# fl3xwatch.net
KiCad netlist of a schematic drawn in EAGLE
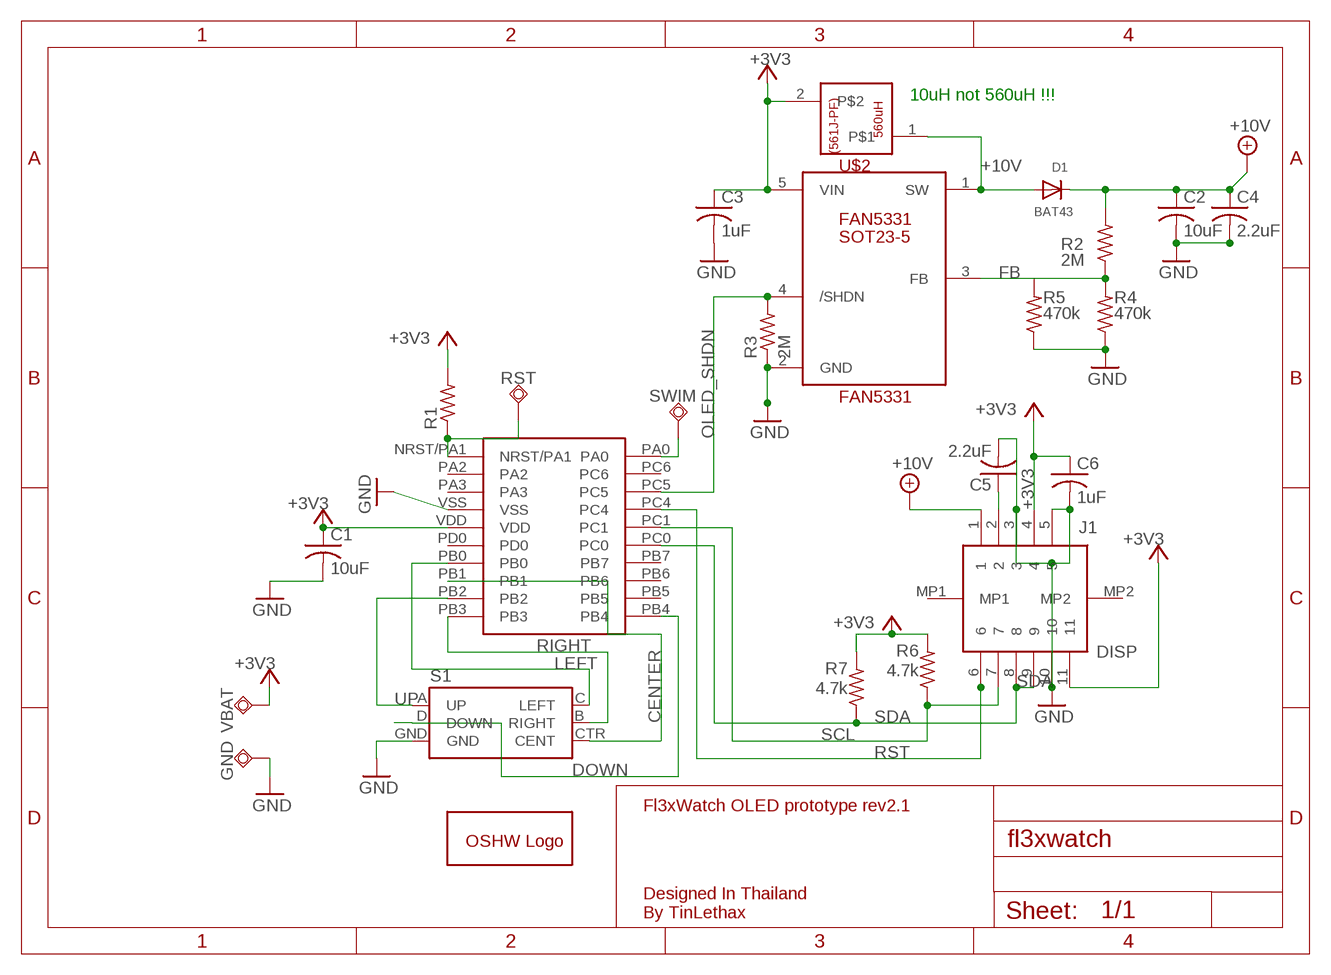
[diagram p0: schematic, sheet 1]

(export (version "E")
  (design (tool "Eeschema 10.0.6"))
  (components
    (comp (ref "C1")
      (value "10uF")
      (footprint "eagle-import:C0805")
      (libsource (lib "eagle-import") (part "C-USC0805"))
    )
    (comp (ref "C2")
      (value "10uF")
      (footprint "eagle-import:C0805")
      (libsource (lib "eagle-import") (part "C-USC0805"))
    )
    (comp (ref "C3")
      (value "1uF")
      (footprint "eagle-import:C0603")
      (libsource (lib "eagle-import") (part "C-USC0603"))
    )
    (comp (ref "C4")
      (value "2.2uF")
      (footprint "eagle-import:C0603")
      (libsource (lib "eagle-import") (part "C-USC0603"))
    )
    (comp (ref "C5")
      (value "2.2uF")
      (footprint "eagle-import:C0603")
      (libsource (lib "eagle-import") (part "C-USC0603"))
    )
    (comp (ref "C6")
      (value "1uF")
      (footprint "eagle-import:C0603")
      (libsource (lib "eagle-import") (part "C-USC0603"))
    )
    (comp (ref "D1")
      (value "BAT43")
      (footprint "eagle-import:SOD-323F")
      (libsource (lib "eagle-import") (part "DIODESOD-323F"))
    )
    (comp (ref "GND")
      (value "TPSQTP20SQ")
      (footprint "eagle-import:TP20SQ")
      (libsource (lib "eagle-import") (part "TPSQTP20SQ"))
    )
    (comp (ref "GOLD_ORB_SM1")
      (value "OSHWLOGOLOGO5MM")
      (footprint "eagle-import:OSHW_5MM")
      (libsource (lib "eagle-import") (part "OSHWLOGOLOGO5MM"))
    )
    (comp (ref "J1")
      (value "DISP")
      (footprint "eagle-import:FH35C11S03SHW50")
      (fields
        (field (name "MANUFACTURER_PART_NUMBER") "FH35C-11S-0.3SHW(50)")
        (field (name "MOUSER_PART_NUMBER") "798-FH35C11S03SHW50")
      )
      (libsource (lib "eagle-import") (part "FH35C-11S-0.3SHW_50_"))
    )
    (comp (ref "L1")
      (value "10uH")
      (footprint "eagle-import:INDC4526X50N")
      (libsource (lib "eagle-import") (part "NL453232T-561J-PF"))
    )
    (comp (ref "R1")
      (value "R-US_R0603")
      (footprint "eagle-import:R0603")
      (libsource (lib "eagle-import") (part "R-US_R0603"))
    )
    (comp (ref "R2")
      (value "2M")
      (footprint "eagle-import:R0603")
      (libsource (lib "eagle-import") (part "R-US_R0603"))
    )
    (comp (ref "R3")
      (value "2M")
      (footprint "eagle-import:R0603")
      (libsource (lib "eagle-import") (part "R-US_R0603"))
    )
    (comp (ref "R4")
      (value "470k")
      (footprint "eagle-import:R0805")
      (libsource (lib "eagle-import") (part "R-US_R0805"))
    )
    (comp (ref "R5")
      (value "470k")
      (footprint "eagle-import:R0805")
      (libsource (lib "eagle-import") (part "R-US_R0805"))
    )
    (comp (ref "R6")
      (value "4.7k")
      (footprint "eagle-import:R0603")
      (libsource (lib "eagle-import") (part "R-US_R0603"))
    )
    (comp (ref "R7")
      (value "4.7k")
      (footprint "eagle-import:R0603")
      (libsource (lib "eagle-import") (part "R-US_R0603"))
    )
    (comp (ref "RST")
      (value "TPSQTP15R")
      (footprint "eagle-import:TP15R")
      (libsource (lib "eagle-import") (part "TPSQTP15R"))
    )
    (comp (ref "S1")
      (value "SPARKFUN-ELECTROMECHANICAL_JOYSTICK_MINI")
      (footprint "eagle-import:SPARKFUN-ELECTROMECHANICAL_JOYSTICK_MINI")
      (libsource (lib "eagle-import") (part "SPARKFUN-ELECTROMECHANICAL_JOYSTICK_MINI"))
    )
    (comp (ref "SWIM")
      (value "TPSQTP15R")
      (footprint "eagle-import:TP15R")
      (libsource (lib "eagle-import") (part "TPSQTP15R"))
    )
    (comp (ref "U$1")
      (value "STM8L151F3")
      (footprint "eagle-import:UFQFPN-20")
      (libsource (lib "eagle-import") (part "STM8L151F3"))
    )
    (comp (ref "U$2")
      (value "FAN5331")
      (footprint "eagle-import:SOT95P280X145-5N")
      (libsource (lib "eagle-import") (part "FAN5331"))
    )
    (comp (ref "VBAT")
      (value "TPSQTP20SQ")
      (footprint "eagle-import:TP20SQ")
      (libsource (lib "eagle-import") (part "TPSQTP20SQ"))
    )
  )
  (nets
    (net (code "1") (name "+3V3") (class "Default")
      (node (ref "C1") (pin "1") (pinfunction "1_1") (pintype "passive"))
      (node (ref "C3") (pin "1") (pinfunction "1_1") (pintype "passive"))
      (node (ref "C6") (pin "1") (pinfunction "1_1") (pintype "passive"))
      (node (ref "J1") (pin "11") (pinfunction "11_11") (pintype "bidirectional"))
      (node (ref "J1") (pin "4") (pinfunction "4_4") (pintype "bidirectional"))
      (node (ref "L1") (pin "2") (pinfunction "P$2_2") (pintype "bidirectional"))
      (node (ref "R1") (pin "2") (pinfunction "2_2") (pintype "passive"))
      (node (ref "R6") (pin "2") (pinfunction "2_2") (pintype "passive"))
      (node (ref "R7") (pin "2") (pinfunction "2_2") (pintype "passive"))
      (node (ref "U$1") (pin "VDD") (pinfunction "VDD_VDD") (pintype "bidirectional"))
      (node (ref "U$2") (pin "5") (pinfunction "VIN_5") (pintype "bidirectional"))
      (node (ref "VBAT") (pin "TP") (pinfunction "TP_TP") (pintype "input"))
    )
    (net (code "2") (name "+10V") (class "Default")
      (node (ref "C2") (pin "1") (pinfunction "1_1") (pintype "passive"))
      (node (ref "C4") (pin "1") (pinfunction "1_1") (pintype "passive"))
      (node (ref "D1") (pin "C") (pinfunction "C_C") (pintype "passive"))
      (node (ref "J1") (pin "1") (pinfunction "1_1") (pintype "bidirectional"))
      (node (ref "R2") (pin "2") (pinfunction "2_2") (pintype "passive"))
    )
    (net (code "3") (name "/CENTER") (class "Default")
      (node (ref "S1") (pin "CTR") (pinfunction "CENT_CTR") (pintype "bidirectional"))
      (node (ref "U$1") (pin "PB1") (pinfunction "PB1_PB1") (pintype "bidirectional"))
    )
    (net (code "4") (name "/DOWN") (class "Default")
      (node (ref "S1") (pin "D") (pinfunction "DOWN_D") (pintype "bidirectional"))
      (node (ref "U$1") (pin "PB4") (pinfunction "PB4_PB4") (pintype "bidirectional"))
    )
    (net (code "5") (name "/FB") (class "Default")
      (node (ref "R2") (pin "1") (pinfunction "1_1") (pintype "passive"))
      (node (ref "R4") (pin "2") (pinfunction "2_2") (pintype "passive"))
      (node (ref "R5") (pin "2") (pinfunction "2_2") (pintype "passive"))
      (node (ref "U$2") (pin "3") (pinfunction "FB_3") (pintype "bidirectional"))
    )
    (net (code "6") (name "/LEFT") (class "Default")
      (node (ref "S1") (pin "C") (pinfunction "LEFT_C") (pintype "bidirectional"))
      (node (ref "U$1") (pin "PB0") (pinfunction "PB0_PB0") (pintype "bidirectional"))
    )
    (net (code "7") (name "/OLED_SHDN") (class "Default")
      (node (ref "R3") (pin "2") (pinfunction "2_2") (pintype "passive"))
      (node (ref "U$1") (pin "PC5") (pinfunction "PC5_PC5") (pintype "bidirectional"))
      (node (ref "U$2") (pin "4") (pinfunction "/SHDN_4") (pintype "bidirectional"))
    )
    (net (code "8") (name "/RIGHT") (class "Default")
      (node (ref "S1") (pin "B") (pinfunction "RIGHT_B") (pintype "bidirectional"))
      (node (ref "U$1") (pin "PB3") (pinfunction "PB3_PB3") (pintype "bidirectional"))
    )
    (net (code "9") (name "/RST") (class "Default")
      (node (ref "J1") (pin "6") (pinfunction "6_6") (pintype "bidirectional"))
      (node (ref "U$1") (pin "PC4") (pinfunction "PC4_PC4") (pintype "bidirectional"))
    )
    (net (code "10") (name "/SCL") (class "Default")
      (node (ref "J1") (pin "7") (pinfunction "7_7") (pintype "bidirectional"))
      (node (ref "R6") (pin "1") (pinfunction "1_1") (pintype "passive"))
      (node (ref "U$1") (pin "PC1") (pinfunction "PC1_PC1") (pintype "bidirectional"))
    )
    (net (code "11") (name "/SDA") (class "Default")
      (node (ref "J1") (pin "8") (pinfunction "8_8") (pintype "bidirectional"))
      (node (ref "J1") (pin "9") (pinfunction "9_9") (pintype "bidirectional"))
      (node (ref "R7") (pin "1") (pinfunction "1_1") (pintype "passive"))
      (node (ref "U$1") (pin "PC0") (pinfunction "PC0_PC0") (pintype "bidirectional"))
    )
    (net (code "12") (name "/UP") (class "Default")
      (node (ref "S1") (pin "A") (pinfunction "UP_A") (pintype "bidirectional"))
      (node (ref "U$1") (pin "PB2") (pinfunction "PB2_PB2") (pintype "bidirectional"))
    )
    (net (code "13") (name "GND") (class "Default")
      (node (ref "C1") (pin "2") (pinfunction "2_2") (pintype "passive"))
      (node (ref "C2") (pin "2") (pinfunction "2_2") (pintype "passive"))
      (node (ref "C3") (pin "2") (pinfunction "2_2") (pintype "passive"))
      (node (ref "C4") (pin "2") (pinfunction "2_2") (pintype "passive"))
      (node (ref "C5") (pin "2") (pinfunction "2_2") (pintype "passive"))
      (node (ref "C6") (pin "2") (pinfunction "2_2") (pintype "passive"))
      (node (ref "GND") (pin "TP") (pinfunction "TP_TP") (pintype "input"))
      (node (ref "J1") (pin "10") (pinfunction "10_10") (pintype "bidirectional"))
      (node (ref "J1") (pin "3") (pinfunction "3_3") (pintype "bidirectional"))
      (node (ref "J1") (pin "5") (pinfunction "5_5") (pintype "bidirectional"))
      (node (ref "R3") (pin "1") (pinfunction "1_1") (pintype "passive"))
      (node (ref "R4") (pin "1") (pinfunction "1_1") (pintype "passive"))
      (node (ref "R5") (pin "1") (pinfunction "1_1") (pintype "passive"))
      (node (ref "S1") (pin "GND") (pinfunction "GND_GND") (pintype "bidirectional"))
      (node (ref "U$1") (pin "VSS") (pinfunction "VSS_VSS") (pintype "bidirectional"))
      (node (ref "U$2") (pin "2") (pinfunction "GND_2") (pintype "bidirectional"))
    )
    (net (code "14") (name "Net-(C5-Pad1)") (class "Default")
      (node (ref "C5") (pin "1") (pinfunction "1_1") (pintype "passive"))
      (node (ref "J1") (pin "2") (pinfunction "2_2") (pintype "bidirectional"))
    )
    (net (code "15") (name "Net-(L1-P$1)") (class "Default")
      (node (ref "D1") (pin "A") (pinfunction "A_A") (pintype "passive"))
      (node (ref "L1") (pin "1") (pinfunction "P$1_1") (pintype "bidirectional"))
      (node (ref "U$2") (pin "1") (pinfunction "SW_1") (pintype "bidirectional"))
    )
    (net (code "16") (name "Net-(R1-Pad1)") (class "Default")
      (node (ref "R1") (pin "1") (pinfunction "1_1") (pintype "passive"))
      (node (ref "RST") (pin "TP") (pinfunction "TP_TP") (pintype "input"))
      (node (ref "U$1") (pin "NRST/PA1") (pinfunction "NRST/PA1_NRST/PA1") (pintype "bidirectional"))
    )
    (net (code "17") (name "Net-(SWIM-PadTP)") (class "Default")
      (node (ref "SWIM") (pin "TP") (pinfunction "TP_TP") (pintype "input"))
      (node (ref "U$1") (pin "PA0") (pinfunction "PA0_PA0") (pintype "bidirectional"))
    )
    (net (code "18") (name "unconnected-(J1-PadMP1)") (class "Default")
      (node (ref "J1") (pin "MP1") (pinfunction "MP1_MP1") (pintype "bidirectional"))
    )
    (net (code "19") (name "unconnected-(J1-PadMP2)") (class "Default")
      (node (ref "J1") (pin "MP2") (pinfunction "MP2_MP2") (pintype "bidirectional"))
    )
    (net (code "20") (name "unconnected-(U$1-PadPA2)") (class "Default")
      (node (ref "U$1") (pin "PA2") (pinfunction "PA2_PA2") (pintype "bidirectional"))
    )
    (net (code "21") (name "unconnected-(U$1-PadPA3)") (class "Default")
      (node (ref "U$1") (pin "PA3") (pinfunction "PA3_PA3") (pintype "bidirectional"))
    )
    (net (code "22") (name "unconnected-(U$1-PadPB5)") (class "Default")
      (node (ref "U$1") (pin "PB5") (pinfunction "PB5_PB5") (pintype "bidirectional"))
    )
    (net (code "23") (name "unconnected-(U$1-PadPB6)") (class "Default")
      (node (ref "U$1") (pin "PB6") (pinfunction "PB6_PB6") (pintype "bidirectional"))
    )
    (net (code "24") (name "unconnected-(U$1-PadPB7)") (class "Default")
      (node (ref "U$1") (pin "PB7") (pinfunction "PB7_PB7") (pintype "bidirectional"))
    )
    (net (code "25") (name "unconnected-(U$1-PadPC6)") (class "Default")
      (node (ref "U$1") (pin "PC6") (pinfunction "PC6_PC6") (pintype "bidirectional"))
    )
    (net (code "26") (name "unconnected-(U$1-PadPD0)") (class "Default")
      (node (ref "U$1") (pin "PD0") (pinfunction "PD0_PD0") (pintype "bidirectional"))
    )
  )
)
